# snc98_Display_15x7-Seg_3-digit_LTD040.net
KiCad netlist of a schematic drawn in EAGLE
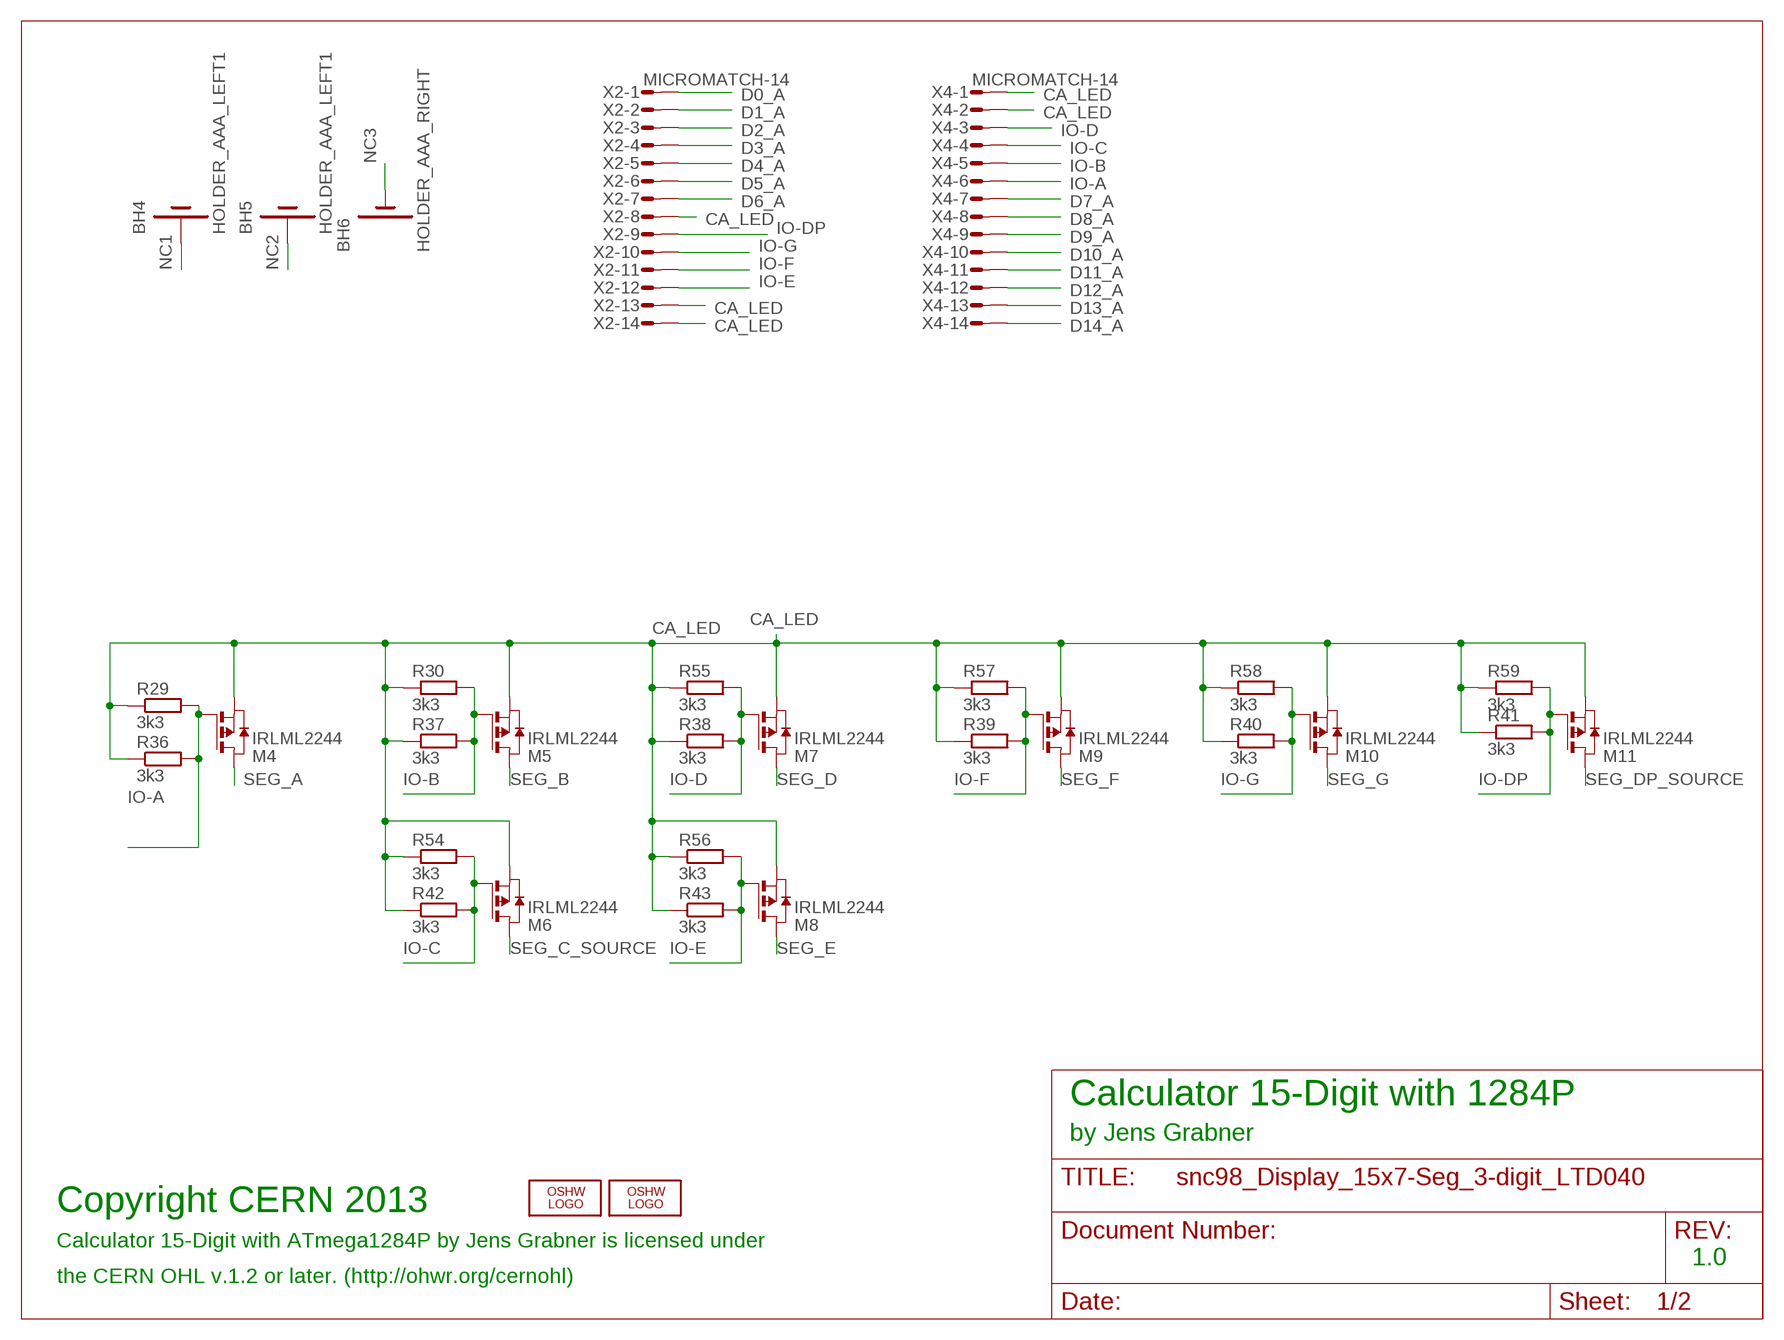
[diagram p0: schematic, sheet 1]
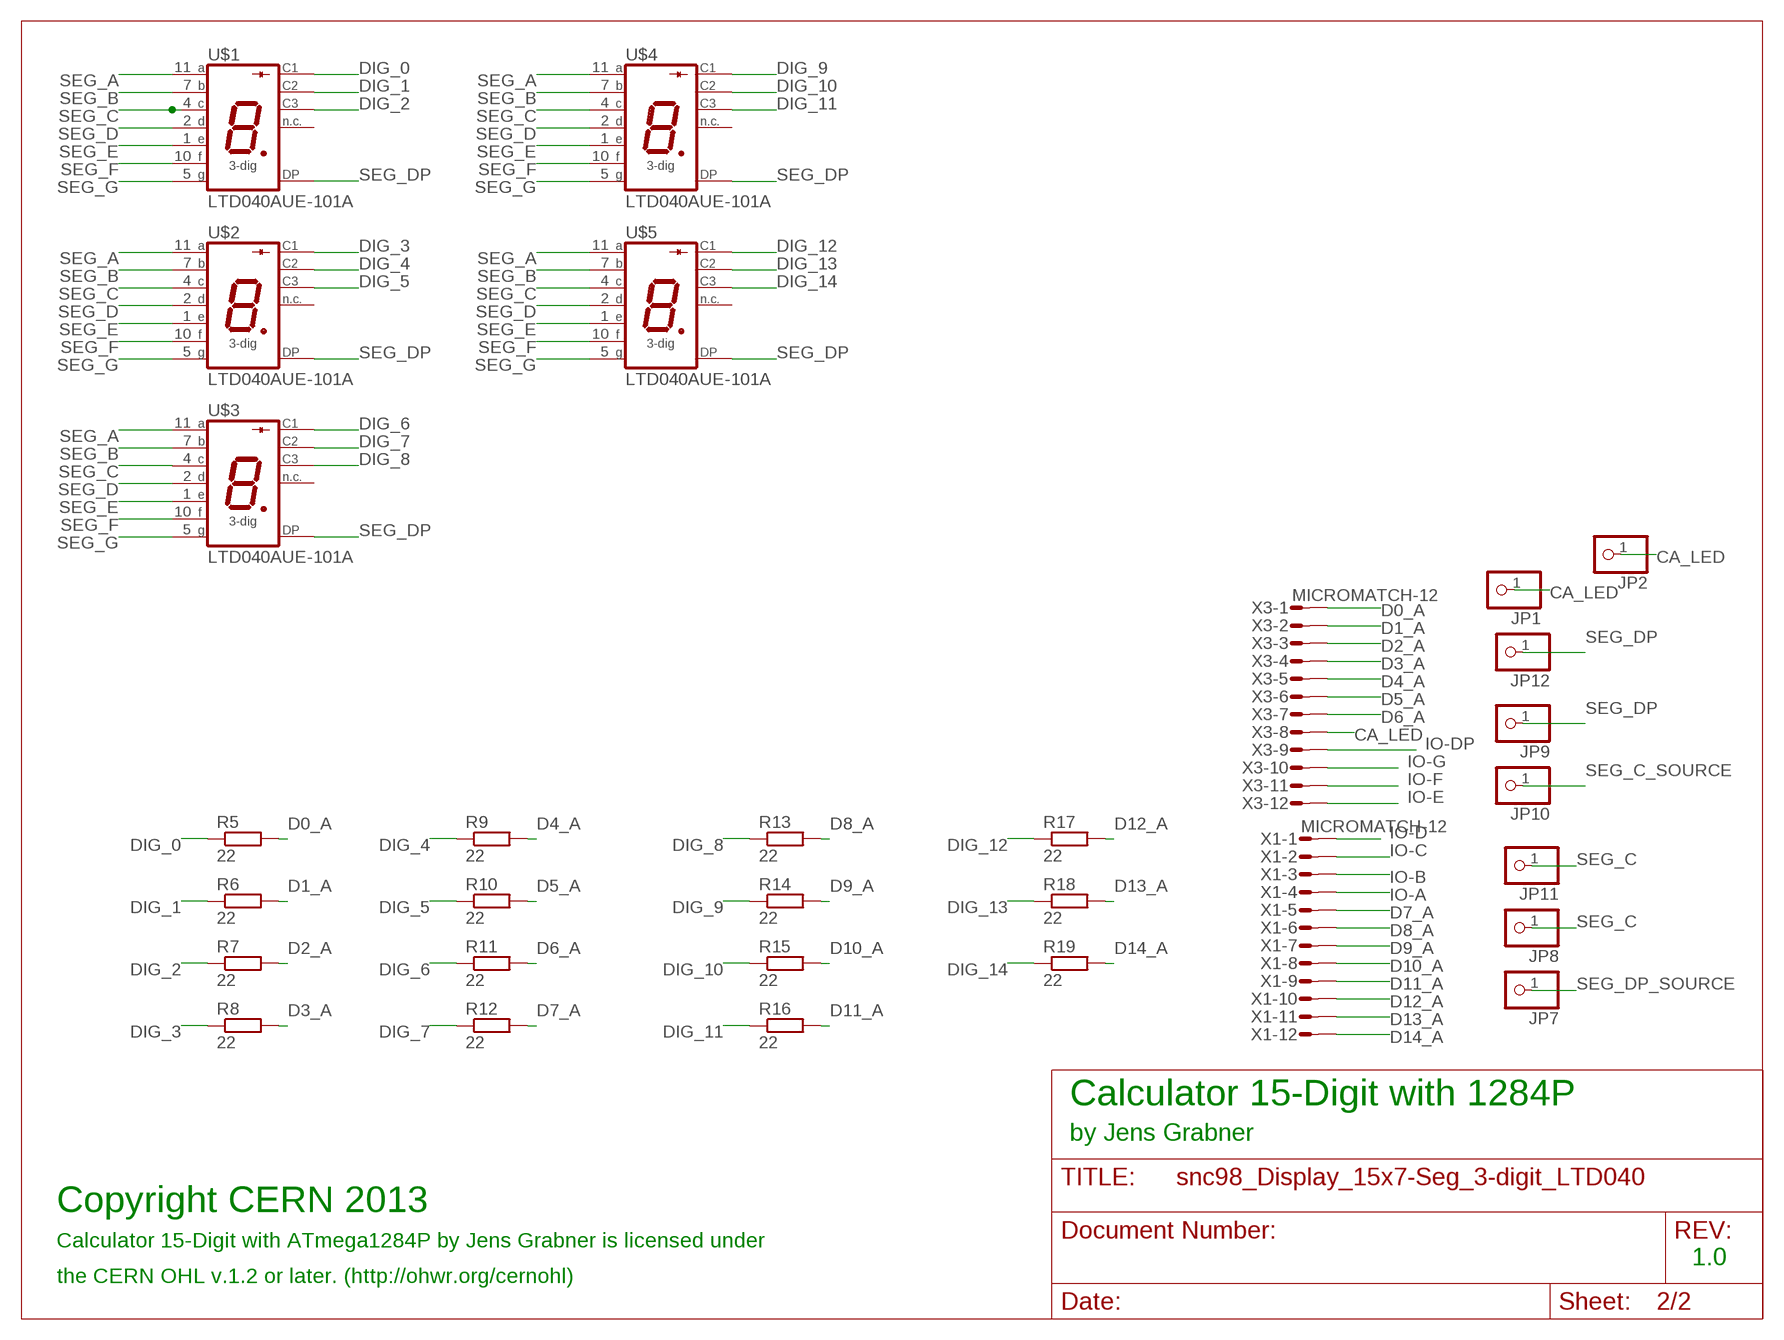
[diagram p1: schematic, sheet 2]

(export (version "E")
  (design (tool "Eeschema 10.0.6"))
  (components
    (comp (ref "JP1")
      (value "PINHD-1X1")
      (footprint "eagle-import:1X01")
      (libsource (lib "eagle-import") (part "PINHD-1X1"))
    )
    (comp (ref "JP2")
      (value "PINHD-1X1")
      (footprint "eagle-import:1X01")
      (libsource (lib "eagle-import") (part "PINHD-1X1"))
    )
    (comp (ref "JP7")
      (value "PINHD-1X1")
      (footprint "eagle-import:1X01")
      (libsource (lib "eagle-import") (part "PINHD-1X1"))
    )
    (comp (ref "JP8")
      (value "PINHD-1X1")
      (footprint "eagle-import:1X01")
      (libsource (lib "eagle-import") (part "PINHD-1X1"))
    )
    (comp (ref "JP9")
      (value "PINHD-1X1")
      (footprint "eagle-import:1X01")
      (libsource (lib "eagle-import") (part "PINHD-1X1"))
    )
    (comp (ref "JP10")
      (value "PINHD-1X1")
      (footprint "eagle-import:1X01")
      (libsource (lib "eagle-import") (part "PINHD-1X1"))
    )
    (comp (ref "JP11")
      (value "PINHD-1X1")
      (footprint "eagle-import:1X01")
      (libsource (lib "eagle-import") (part "PINHD-1X1"))
    )
    (comp (ref "JP12")
      (value "PINHD-1X1")
      (footprint "eagle-import:1X01")
      (libsource (lib "eagle-import") (part "PINHD-1X1"))
    )
    (comp (ref "R5")
      (value "22")
      (footprint "eagle-import:R1210")
      (libsource (lib "eagle-import") (part "R-EU_R1210"))
    )
    (comp (ref "R6")
      (value "22")
      (footprint "eagle-import:R1210")
      (libsource (lib "eagle-import") (part "R-EU_R1210"))
    )
    (comp (ref "R7")
      (value "22")
      (footprint "eagle-import:R1210")
      (libsource (lib "eagle-import") (part "R-EU_R1210"))
    )
    (comp (ref "R8")
      (value "22")
      (footprint "eagle-import:R1210")
      (libsource (lib "eagle-import") (part "R-EU_R1210"))
    )
    (comp (ref "R9")
      (value "22")
      (footprint "eagle-import:R1210")
      (libsource (lib "eagle-import") (part "R-EU_R1210"))
    )
    (comp (ref "R10")
      (value "22")
      (footprint "eagle-import:R1210")
      (libsource (lib "eagle-import") (part "R-EU_R1210"))
    )
    (comp (ref "R11")
      (value "22")
      (footprint "eagle-import:R1210")
      (libsource (lib "eagle-import") (part "R-EU_R1210"))
    )
    (comp (ref "R12")
      (value "22")
      (footprint "eagle-import:R1210")
      (libsource (lib "eagle-import") (part "R-EU_R1210"))
    )
    (comp (ref "R13")
      (value "22")
      (footprint "eagle-import:R1210")
      (libsource (lib "eagle-import") (part "R-EU_R1210"))
    )
    (comp (ref "R14")
      (value "22")
      (footprint "eagle-import:R1210")
      (libsource (lib "eagle-import") (part "R-EU_R1210"))
    )
    (comp (ref "R15")
      (value "22")
      (footprint "eagle-import:R1210")
      (libsource (lib "eagle-import") (part "R-EU_R1210"))
    )
    (comp (ref "R16")
      (value "22")
      (footprint "eagle-import:R1210")
      (libsource (lib "eagle-import") (part "R-EU_R1210"))
    )
    (comp (ref "R17")
      (value "22")
      (footprint "eagle-import:R1210")
      (libsource (lib "eagle-import") (part "R-EU_R1210"))
    )
    (comp (ref "R18")
      (value "22")
      (footprint "eagle-import:R1210")
      (libsource (lib "eagle-import") (part "R-EU_R1210"))
    )
    (comp (ref "R19")
      (value "22")
      (footprint "eagle-import:R1210")
      (libsource (lib "eagle-import") (part "R-EU_R1210"))
    )
    (comp (ref "U$1")
      (value "LTD040AUE-101A")
      (footprint "eagle-import:LTD040AUE-101A")
      (libsource (lib "eagle-import") (part "LTD040AUE-101A"))
    )
    (comp (ref "U$2")
      (value "LTD040AUE-101A")
      (footprint "eagle-import:LTD040AUE-101A")
      (libsource (lib "eagle-import") (part "LTD040AUE-101A"))
    )
    (comp (ref "U$3")
      (value "LTD040AUE-101A")
      (footprint "eagle-import:LTD040AUE-101A")
      (libsource (lib "eagle-import") (part "LTD040AUE-101A"))
    )
    (comp (ref "U$4")
      (value "LTD040AUE-101A")
      (footprint "eagle-import:LTD040AUE-101A")
      (libsource (lib "eagle-import") (part "LTD040AUE-101A"))
    )
    (comp (ref "U$5")
      (value "LTD040AUE-101A")
      (footprint "eagle-import:LTD040AUE-101A")
      (libsource (lib "eagle-import") (part "LTD040AUE-101A"))
    )
    (comp (ref "X1")
      (value "MICROMATCH-12")
      (footprint "eagle-import:MICROMATCH-12")
      (fields (field (name "MF") "FARNELL") (field (name "MPN") "8-215464-2"))
      (libsource (lib "eagle-import") (part "MICROMATCH-12"))
    )
    (comp (ref "X3")
      (value "MICROMATCH-12")
      (footprint "eagle-import:MICROMATCH-12")
      (fields (field (name "MF") "FARNELL") (field (name "MPN") "8-215464-2"))
      (libsource (lib "eagle-import") (part "MICROMATCH-12"))
    )
    (comp (ref "BH4")
      (value "HOLDER_AAA_LEFT1")
      (footprint "eagle-import:BATTERY-AAA-LEFT")
      (libsource (lib "eagle-import") (part "HOLDER_AAA_LEFT1"))
    )
    (comp (ref "BH5")
      (value "HOLDER_AAA_LEFT1")
      (footprint "eagle-import:BATTERY-AAA-LEFT")
      (libsource (lib "eagle-import") (part "HOLDER_AAA_LEFT1"))
    )
    (comp (ref "BH6")
      (value "HOLDER_AAA_RIGHT")
      (footprint "eagle-import:BATTERY-AAA-RIGHT")
      (libsource (lib "eagle-import") (part "HOLDER_AAA_RIGHT"))
    )
    (comp (ref "LOGO1")
      (value "OSHW_LOGO_8MILX0150-NT")
      (footprint "eagle-import:OSHW_8X150_NOTEXT")
      (libsource (lib "eagle-import") (part "OSHW_LOGO_8MILX0150-NT"))
    )
    (comp (ref "LOGO3")
      (value "OSHW_LOGO_6MILX0100-NT")
      (footprint "eagle-import:OSHW_6X100_NOTEXT")
      (libsource (lib "eagle-import") (part "OSHW_LOGO_6MILX0100-NT"))
    )
    (comp (ref "M4")
      (value "IRLML2244")
      (footprint "eagle-import:SOT-23")
      (libsource (lib "eagle-import") (part "IRLML6402"))
    )
    (comp (ref "M5")
      (value "IRLML2244")
      (footprint "eagle-import:SOT-23")
      (libsource (lib "eagle-import") (part "IRLML6402"))
    )
    (comp (ref "M6")
      (value "IRLML2244")
      (footprint "eagle-import:SOT-23")
      (libsource (lib "eagle-import") (part "IRLML6402"))
    )
    (comp (ref "M7")
      (value "IRLML2244")
      (footprint "eagle-import:SOT-23")
      (libsource (lib "eagle-import") (part "IRLML6402"))
    )
    (comp (ref "M8")
      (value "IRLML2244")
      (footprint "eagle-import:SOT-23")
      (libsource (lib "eagle-import") (part "IRLML6402"))
    )
    (comp (ref "M9")
      (value "IRLML2244")
      (footprint "eagle-import:SOT-23")
      (libsource (lib "eagle-import") (part "IRLML6402"))
    )
    (comp (ref "M10")
      (value "IRLML2244")
      (footprint "eagle-import:SOT-23")
      (libsource (lib "eagle-import") (part "IRLML6402"))
    )
    (comp (ref "M11")
      (value "IRLML2244")
      (footprint "eagle-import:SOT-23")
      (libsource (lib "eagle-import") (part "IRLML6402"))
    )
    (comp (ref "R29")
      (value "3k3")
      (footprint "eagle-import:0204_5")
      (libsource (lib "eagle-import") (part "R-EU_0204/5"))
    )
    (comp (ref "R30")
      (value "3k3")
      (footprint "eagle-import:0204_5")
      (libsource (lib "eagle-import") (part "R-EU_0204/5"))
    )
    (comp (ref "R36")
      (value "3k3")
      (footprint "eagle-import:R1206")
      (libsource (lib "eagle-import") (part "R-EU_R1206"))
    )
    (comp (ref "R37")
      (value "3k3")
      (footprint "eagle-import:R1206")
      (libsource (lib "eagle-import") (part "R-EU_R1206"))
    )
    (comp (ref "R38")
      (value "3k3")
      (footprint "eagle-import:R1206")
      (libsource (lib "eagle-import") (part "R-EU_R1206"))
    )
    (comp (ref "R39")
      (value "3k3")
      (footprint "eagle-import:R1206")
      (libsource (lib "eagle-import") (part "R-EU_R1206"))
    )
    (comp (ref "R40")
      (value "3k3")
      (footprint "eagle-import:R1206")
      (libsource (lib "eagle-import") (part "R-EU_R1206"))
    )
    (comp (ref "R41")
      (value "3k3")
      (footprint "eagle-import:R1206")
      (libsource (lib "eagle-import") (part "R-EU_R1206"))
    )
    (comp (ref "R42")
      (value "3k3")
      (footprint "eagle-import:R1206")
      (libsource (lib "eagle-import") (part "R-EU_R1206"))
    )
    (comp (ref "R43")
      (value "3k3")
      (footprint "eagle-import:R1206")
      (libsource (lib "eagle-import") (part "R-EU_R1206"))
    )
    (comp (ref "R54")
      (value "3k3")
      (footprint "eagle-import:0204_5")
      (libsource (lib "eagle-import") (part "R-EU_0204/5"))
    )
    (comp (ref "R55")
      (value "3k3")
      (footprint "eagle-import:0204_5")
      (libsource (lib "eagle-import") (part "R-EU_0204/5"))
    )
    (comp (ref "R56")
      (value "3k3")
      (footprint "eagle-import:0204_5")
      (libsource (lib "eagle-import") (part "R-EU_0204/5"))
    )
    (comp (ref "R57")
      (value "3k3")
      (footprint "eagle-import:0204_5")
      (libsource (lib "eagle-import") (part "R-EU_0204/5"))
    )
    (comp (ref "R58")
      (value "3k3")
      (footprint "eagle-import:0204_5")
      (libsource (lib "eagle-import") (part "R-EU_0204/5"))
    )
    (comp (ref "R59")
      (value "3k3")
      (footprint "eagle-import:0204_5")
      (libsource (lib "eagle-import") (part "R-EU_0204/5"))
    )
    (comp (ref "X2")
      (value "MICROMATCH-14")
      (footprint "eagle-import:MICROMATCH-14")
      (fields (field (name "MF") "FARNELL") (field (name "MPN") "8-215464-4"))
      (libsource (lib "eagle-import") (part "MICROMATCH-14"))
    )
    (comp (ref "X4")
      (value "MICROMATCH-14")
      (footprint "eagle-import:MICROMATCH-14")
      (fields (field (name "MF") "FARNELL") (field (name "MPN") "8-215464-4"))
      (libsource (lib "eagle-import") (part "MICROMATCH-14"))
    )
  )
  (nets
    (net (code "1") (name "CA_LED") (class "Default")
      (node (ref "JP1") (pin "1") (pinfunction "1_1") (pintype "passive"))
      (node (ref "JP2") (pin "1") (pinfunction "1_1") (pintype "passive"))
      (node (ref "M10") (pin "2") (pinfunction "S_2") (pintype "passive"))
      (node (ref "M11") (pin "2") (pinfunction "S_2") (pintype "passive"))
      (node (ref "M4") (pin "2") (pinfunction "S_2") (pintype "passive"))
      (node (ref "M5") (pin "2") (pinfunction "S_2") (pintype "passive"))
      (node (ref "M6") (pin "2") (pinfunction "S_2") (pintype "passive"))
      (node (ref "M7") (pin "2") (pinfunction "S_2") (pintype "passive"))
      (node (ref "M8") (pin "2") (pinfunction "S_2") (pintype "passive"))
      (node (ref "M9") (pin "2") (pinfunction "S_2") (pintype "passive"))
      (node (ref "R29") (pin "1") (pinfunction "1_1") (pintype "passive"))
      (node (ref "R30") (pin "1") (pinfunction "1_1") (pintype "passive"))
      (node (ref "R36") (pin "1") (pinfunction "1_1") (pintype "passive"))
      (node (ref "R37") (pin "1") (pinfunction "1_1") (pintype "passive"))
      (node (ref "R38") (pin "1") (pinfunction "1_1") (pintype "passive"))
      (node (ref "R39") (pin "1") (pinfunction "1_1") (pintype "passive"))
      (node (ref "R40") (pin "1") (pinfunction "1_1") (pintype "passive"))
      (node (ref "R41") (pin "1") (pinfunction "1_1") (pintype "passive"))
      (node (ref "R42") (pin "1") (pinfunction "1_1") (pintype "passive"))
      (node (ref "R43") (pin "1") (pinfunction "1_1") (pintype "passive"))
      (node (ref "R54") (pin "1") (pinfunction "1_1") (pintype "passive"))
      (node (ref "R55") (pin "1") (pinfunction "1_1") (pintype "passive"))
      (node (ref "R56") (pin "1") (pinfunction "1_1") (pintype "passive"))
      (node (ref "R57") (pin "1") (pinfunction "1_1") (pintype "passive"))
      (node (ref "R58") (pin "1") (pinfunction "1_1") (pintype "passive"))
      (node (ref "R59") (pin "1") (pinfunction "1_1") (pintype "passive"))
      (node (ref "X2") (pin "13") (pinfunction "S_13") (pintype "passive"))
      (node (ref "X2") (pin "14") (pinfunction "S_14") (pintype "passive"))
      (node (ref "X2") (pin "8") (pinfunction "S_8") (pintype "passive"))
      (node (ref "X3") (pin "8") (pinfunction "S_8") (pintype "passive"))
      (node (ref "X4") (pin "1") (pinfunction "S_1") (pintype "passive"))
      (node (ref "X4") (pin "2") (pinfunction "S_2") (pintype "passive"))
    )
    (net (code "2") (name "D0_A") (class "Default")
      (node (ref "R5") (pin "2") (pinfunction "2_2") (pintype "passive"))
      (node (ref "X2") (pin "1") (pinfunction "S_1") (pintype "passive"))
      (node (ref "X3") (pin "1") (pinfunction "S_1") (pintype "passive"))
    )
    (net (code "3") (name "D1_A") (class "Default")
      (node (ref "R6") (pin "2") (pinfunction "2_2") (pintype "passive"))
      (node (ref "X2") (pin "2") (pinfunction "S_2") (pintype "passive"))
      (node (ref "X3") (pin "2") (pinfunction "S_2") (pintype "passive"))
    )
    (net (code "4") (name "D2_A") (class "Default")
      (node (ref "R7") (pin "2") (pinfunction "2_2") (pintype "passive"))
      (node (ref "X2") (pin "3") (pinfunction "S_3") (pintype "passive"))
      (node (ref "X3") (pin "3") (pinfunction "S_3") (pintype "passive"))
    )
    (net (code "5") (name "D3_A") (class "Default")
      (node (ref "R8") (pin "2") (pinfunction "2_2") (pintype "passive"))
      (node (ref "X2") (pin "4") (pinfunction "S_4") (pintype "passive"))
      (node (ref "X3") (pin "4") (pinfunction "S_4") (pintype "passive"))
    )
    (net (code "6") (name "D4_A") (class "Default")
      (node (ref "R9") (pin "2") (pinfunction "2_2") (pintype "passive"))
      (node (ref "X2") (pin "5") (pinfunction "S_5") (pintype "passive"))
      (node (ref "X3") (pin "5") (pinfunction "S_5") (pintype "passive"))
    )
    (net (code "7") (name "D5_A") (class "Default")
      (node (ref "R10") (pin "2") (pinfunction "2_2") (pintype "passive"))
      (node (ref "X2") (pin "6") (pinfunction "S_6") (pintype "passive"))
      (node (ref "X3") (pin "6") (pinfunction "S_6") (pintype "passive"))
    )
    (net (code "8") (name "D6_A") (class "Default")
      (node (ref "R11") (pin "2") (pinfunction "2_2") (pintype "passive"))
      (node (ref "X2") (pin "7") (pinfunction "S_7") (pintype "passive"))
      (node (ref "X3") (pin "7") (pinfunction "S_7") (pintype "passive"))
    )
    (net (code "9") (name "D7_A") (class "Default")
      (node (ref "R12") (pin "2") (pinfunction "2_2") (pintype "passive"))
      (node (ref "X1") (pin "5") (pinfunction "S_5") (pintype "passive"))
      (node (ref "X4") (pin "7") (pinfunction "S_7") (pintype "passive"))
    )
    (net (code "10") (name "D8_A") (class "Default")
      (node (ref "R13") (pin "2") (pinfunction "2_2") (pintype "passive"))
      (node (ref "X1") (pin "6") (pinfunction "S_6") (pintype "passive"))
      (node (ref "X4") (pin "8") (pinfunction "S_8") (pintype "passive"))
    )
    (net (code "11") (name "D9_A") (class "Default")
      (node (ref "R14") (pin "2") (pinfunction "2_2") (pintype "passive"))
      (node (ref "X1") (pin "7") (pinfunction "S_7") (pintype "passive"))
      (node (ref "X4") (pin "9") (pinfunction "S_9") (pintype "passive"))
    )
    (net (code "12") (name "D10_A") (class "Default")
      (node (ref "R15") (pin "2") (pinfunction "2_2") (pintype "passive"))
      (node (ref "X1") (pin "8") (pinfunction "S_8") (pintype "passive"))
      (node (ref "X4") (pin "10") (pinfunction "S_10") (pintype "passive"))
    )
    (net (code "13") (name "D11_A") (class "Default")
      (node (ref "R16") (pin "2") (pinfunction "2_2") (pintype "passive"))
      (node (ref "X1") (pin "9") (pinfunction "S_9") (pintype "passive"))
      (node (ref "X4") (pin "11") (pinfunction "S_11") (pintype "passive"))
    )
    (net (code "14") (name "D12_A") (class "Default")
      (node (ref "R17") (pin "2") (pinfunction "2_2") (pintype "passive"))
      (node (ref "X1") (pin "10") (pinfunction "S_10") (pintype "passive"))
      (node (ref "X4") (pin "12") (pinfunction "S_12") (pintype "passive"))
    )
    (net (code "15") (name "D13_A") (class "Default")
      (node (ref "R18") (pin "2") (pinfunction "2_2") (pintype "passive"))
      (node (ref "X1") (pin "11") (pinfunction "S_11") (pintype "passive"))
      (node (ref "X4") (pin "13") (pinfunction "S_13") (pintype "passive"))
    )
    (net (code "16") (name "D14_A") (class "Default")
      (node (ref "R19") (pin "2") (pinfunction "2_2") (pintype "passive"))
      (node (ref "X1") (pin "12") (pinfunction "S_12") (pintype "passive"))
      (node (ref "X4") (pin "14") (pinfunction "S_14") (pintype "passive"))
    )
    (net (code "17") (name "DIG_0") (class "Default")
      (node (ref "R5") (pin "1") (pinfunction "1_1") (pintype "passive"))
      (node (ref "U$1") (pin "12") (pinfunction "C1_12") (pintype "passive"))
    )
    (net (code "18") (name "DIG_1") (class "Default")
      (node (ref "R6") (pin "1") (pinfunction "1_1") (pintype "passive"))
      (node (ref "U$1") (pin "9") (pinfunction "C2_9") (pintype "passive"))
    )
    (net (code "19") (name "DIG_2") (class "Default")
      (node (ref "R7") (pin "1") (pinfunction "1_1") (pintype "passive"))
      (node (ref "U$1") (pin "8") (pinfunction "C3_8") (pintype "passive"))
    )
    (net (code "20") (name "DIG_3") (class "Default")
      (node (ref "R8") (pin "1") (pinfunction "1_1") (pintype "passive"))
      (node (ref "U$2") (pin "12") (pinfunction "C1_12") (pintype "passive"))
    )
    (net (code "21") (name "DIG_4") (class "Default")
      (node (ref "R9") (pin "1") (pinfunction "1_1") (pintype "passive"))
      (node (ref "U$2") (pin "9") (pinfunction "C2_9") (pintype "passive"))
    )
    (net (code "22") (name "DIG_5") (class "Default")
      (node (ref "R10") (pin "1") (pinfunction "1_1") (pintype "passive"))
      (node (ref "U$2") (pin "8") (pinfunction "C3_8") (pintype "passive"))
    )
    (net (code "23") (name "DIG_6") (class "Default")
      (node (ref "R11") (pin "1") (pinfunction "1_1") (pintype "passive"))
      (node (ref "U$3") (pin "12") (pinfunction "C1_12") (pintype "passive"))
    )
    (net (code "24") (name "DIG_7") (class "Default")
      (node (ref "R12") (pin "1") (pinfunction "1_1") (pintype "passive"))
      (node (ref "U$3") (pin "9") (pinfunction "C2_9") (pintype "passive"))
    )
    (net (code "25") (name "DIG_8") (class "Default")
      (node (ref "R13") (pin "1") (pinfunction "1_1") (pintype "passive"))
      (node (ref "U$3") (pin "8") (pinfunction "C3_8") (pintype "passive"))
    )
    (net (code "26") (name "DIG_9") (class "Default")
      (node (ref "R14") (pin "1") (pinfunction "1_1") (pintype "passive"))
      (node (ref "U$4") (pin "12") (pinfunction "C1_12") (pintype "passive"))
    )
    (net (code "27") (name "DIG_10") (class "Default")
      (node (ref "R15") (pin "1") (pinfunction "1_1") (pintype "passive"))
      (node (ref "U$4") (pin "9") (pinfunction "C2_9") (pintype "passive"))
    )
    (net (code "28") (name "DIG_11") (class "Default")
      (node (ref "R16") (pin "1") (pinfunction "1_1") (pintype "passive"))
      (node (ref "U$4") (pin "8") (pinfunction "C3_8") (pintype "passive"))
    )
    (net (code "29") (name "DIG_12") (class "Default")
      (node (ref "R17") (pin "1") (pinfunction "1_1") (pintype "passive"))
      (node (ref "U$5") (pin "12") (pinfunction "C1_12") (pintype "passive"))
    )
    (net (code "30") (name "DIG_13") (class "Default")
      (node (ref "R18") (pin "1") (pinfunction "1_1") (pintype "passive"))
      (node (ref "U$5") (pin "9") (pinfunction "C2_9") (pintype "passive"))
    )
    (net (code "31") (name "DIG_14") (class "Default")
      (node (ref "R19") (pin "1") (pinfunction "1_1") (pintype "passive"))
      (node (ref "U$5") (pin "8") (pinfunction "C3_8") (pintype "passive"))
    )
    (net (code "32") (name "IO-A") (class "Default")
      (node (ref "M4") (pin "1") (pinfunction "G_1") (pintype "passive"))
      (node (ref "R29") (pin "2") (pinfunction "2_2") (pintype "passive"))
      (node (ref "R36") (pin "2") (pinfunction "2_2") (pintype "passive"))
      (node (ref "X1") (pin "4") (pinfunction "S_4") (pintype "passive"))
      (node (ref "X4") (pin "6") (pinfunction "S_6") (pintype "passive"))
    )
    (net (code "33") (name "IO-B") (class "Default")
      (node (ref "M5") (pin "1") (pinfunction "G_1") (pintype "passive"))
      (node (ref "R30") (pin "2") (pinfunction "2_2") (pintype "passive"))
      (node (ref "R37") (pin "2") (pinfunction "2_2") (pintype "passive"))
      (node (ref "X1") (pin "3") (pinfunction "S_3") (pintype "passive"))
      (node (ref "X4") (pin "5") (pinfunction "S_5") (pintype "passive"))
    )
    (net (code "34") (name "IO-C") (class "Default")
      (node (ref "M6") (pin "1") (pinfunction "G_1") (pintype "passive"))
      (node (ref "R42") (pin "2") (pinfunction "2_2") (pintype "passive"))
      (node (ref "R54") (pin "2") (pinfunction "2_2") (pintype "passive"))
      (node (ref "X1") (pin "2") (pinfunction "S_2") (pintype "passive"))
      (node (ref "X4") (pin "4") (pinfunction "S_4") (pintype "passive"))
    )
    (net (code "35") (name "IO-D") (class "Default")
      (node (ref "M7") (pin "1") (pinfunction "G_1") (pintype "passive"))
      (node (ref "R38") (pin "2") (pinfunction "2_2") (pintype "passive"))
      (node (ref "R55") (pin "2") (pinfunction "2_2") (pintype "passive"))
      (node (ref "X1") (pin "1") (pinfunction "S_1") (pintype "passive"))
      (node (ref "X4") (pin "3") (pinfunction "S_3") (pintype "passive"))
    )
    (net (code "36") (name "IO-DP") (class "Default")
      (node (ref "M11") (pin "1") (pinfunction "G_1") (pintype "passive"))
      (node (ref "R41") (pin "2") (pinfunction "2_2") (pintype "passive"))
      (node (ref "R59") (pin "2") (pinfunction "2_2") (pintype "passive"))
      (node (ref "X2") (pin "9") (pinfunction "S_9") (pintype "passive"))
      (node (ref "X3") (pin "9") (pinfunction "S_9") (pintype "passive"))
    )
    (net (code "37") (name "IO-E") (class "Default")
      (node (ref "M8") (pin "1") (pinfunction "G_1") (pintype "passive"))
      (node (ref "R43") (pin "2") (pinfunction "2_2") (pintype "passive"))
      (node (ref "R56") (pin "2") (pinfunction "2_2") (pintype "passive"))
      (node (ref "X2") (pin "12") (pinfunction "S_12") (pintype "passive"))
      (node (ref "X3") (pin "12") (pinfunction "S_12") (pintype "passive"))
    )
    (net (code "38") (name "IO-F") (class "Default")
      (node (ref "M9") (pin "1") (pinfunction "G_1") (pintype "passive"))
      (node (ref "R39") (pin "2") (pinfunction "2_2") (pintype "passive"))
      (node (ref "R57") (pin "2") (pinfunction "2_2") (pintype "passive"))
      (node (ref "X2") (pin "11") (pinfunction "S_11") (pintype "passive"))
      (node (ref "X3") (pin "11") (pinfunction "S_11") (pintype "passive"))
    )
    (net (code "39") (name "IO-G") (class "Default")
      (node (ref "M10") (pin "1") (pinfunction "G_1") (pintype "passive"))
      (node (ref "R40") (pin "2") (pinfunction "2_2") (pintype "passive"))
      (node (ref "R58") (pin "2") (pinfunction "2_2") (pintype "passive"))
      (node (ref "X2") (pin "10") (pinfunction "S_10") (pintype "passive"))
      (node (ref "X3") (pin "10") (pinfunction "S_10") (pintype "passive"))
    )
    (net (code "40") (name "NC1") (class "Default")
      (node (ref "BH4") (pin "P1") (pinfunction "+_P1") (pintype "power_in"))
      (node (ref "BH4") (pin "P2") (pinfunction "+_P2") (pintype "power_in"))
      (node (ref "BH4") (pin "P3") (pinfunction "+_P3") (pintype "power_in"))
      (node (ref "BH4") (pin "P4") (pinfunction "+_P4") (pintype "power_in"))
    )
    (net (code "41") (name "NC2") (class "Default")
      (node (ref "BH5") (pin "P1") (pinfunction "+_P1") (pintype "power_in"))
      (node (ref "BH5") (pin "P2") (pinfunction "+_P2") (pintype "power_in"))
      (node (ref "BH5") (pin "P3") (pinfunction "+_P3") (pintype "power_in"))
      (node (ref "BH5") (pin "P4") (pinfunction "+_P4") (pintype "power_in"))
    )
    (net (code "42") (name "NC3") (class "Default")
      (node (ref "BH6") (pin "M1") (pinfunction "-_M1") (pintype "power_in"))
      (node (ref "BH6") (pin "M2") (pinfunction "-_M2") (pintype "power_in"))
      (node (ref "BH6") (pin "M3") (pinfunction "-_M3") (pintype "power_in"))
      (node (ref "BH6") (pin "M4") (pinfunction "-_M4") (pintype "power_in"))
    )
    (net (code "43") (name "SEG_A") (class "Default")
      (node (ref "M4") (pin "3") (pinfunction "D_3") (pintype "passive"))
      (node (ref "U$1") (pin "11") (pinfunction "A_11") (pintype "passive"))
      (node (ref "U$2") (pin "11") (pinfunction "A_11") (pintype "passive"))
      (node (ref "U$3") (pin "11") (pinfunction "A_11") (pintype "passive"))
      (node (ref "U$4") (pin "11") (pinfunction "A_11") (pintype "passive"))
      (node (ref "U$5") (pin "11") (pinfunction "A_11") (pintype "passive"))
    )
    (net (code "44") (name "SEG_B") (class "Default")
      (node (ref "M5") (pin "3") (pinfunction "D_3") (pintype "passive"))
      (node (ref "U$1") (pin "7") (pinfunction "B_7") (pintype "passive"))
      (node (ref "U$2") (pin "7") (pinfunction "B_7") (pintype "passive"))
      (node (ref "U$3") (pin "7") (pinfunction "B_7") (pintype "passive"))
      (node (ref "U$4") (pin "7") (pinfunction "B_7") (pintype "passive"))
      (node (ref "U$5") (pin "7") (pinfunction "B_7") (pintype "passive"))
    )
    (net (code "45") (name "SEG_C") (class "Default")
      (node (ref "JP11") (pin "1") (pinfunction "1_1") (pintype "passive"))
      (node (ref "JP8") (pin "1") (pinfunction "1_1") (pintype "passive"))
      (node (ref "U$1") (pin "4") (pinfunction "C_4") (pintype "passive"))
      (node (ref "U$2") (pin "4") (pinfunction "C_4") (pintype "passive"))
      (node (ref "U$3") (pin "4") (pinfunction "C_4") (pintype "passive"))
      (node (ref "U$4") (pin "4") (pinfunction "C_4") (pintype "passive"))
      (node (ref "U$5") (pin "4") (pinfunction "C_4") (pintype "passive"))
    )
    (net (code "46") (name "SEG_C_SOURCE") (class "Default")
      (node (ref "JP10") (pin "1") (pinfunction "1_1") (pintype "passive"))
      (node (ref "M6") (pin "3") (pinfunction "D_3") (pintype "passive"))
    )
    (net (code "47") (name "SEG_D") (class "Default")
      (node (ref "M7") (pin "3") (pinfunction "D_3") (pintype "passive"))
      (node (ref "U$1") (pin "2") (pinfunction "D_2") (pintype "passive"))
      (node (ref "U$2") (pin "2") (pinfunction "D_2") (pintype "passive"))
      (node (ref "U$3") (pin "2") (pinfunction "D_2") (pintype "passive"))
      (node (ref "U$4") (pin "2") (pinfunction "D_2") (pintype "passive"))
      (node (ref "U$5") (pin "2") (pinfunction "D_2") (pintype "passive"))
    )
    (net (code "48") (name "SEG_DP") (class "Default")
      (node (ref "JP12") (pin "1") (pinfunction "1_1") (pintype "passive"))
      (node (ref "JP9") (pin "1") (pinfunction "1_1") (pintype "passive"))
      (node (ref "U$1") (pin "3") (pinfunction "DP_3") (pintype "passive"))
      (node (ref "U$2") (pin "3") (pinfunction "DP_3") (pintype "passive"))
      (node (ref "U$3") (pin "3") (pinfunction "DP_3") (pintype "passive"))
      (node (ref "U$4") (pin "3") (pinfunction "DP_3") (pintype "passive"))
      (node (ref "U$5") (pin "3") (pinfunction "DP_3") (pintype "passive"))
    )
    (net (code "49") (name "SEG_DP_SOURCE") (class "Default")
      (node (ref "JP7") (pin "1") (pinfunction "1_1") (pintype "passive"))
      (node (ref "M11") (pin "3") (pinfunction "D_3") (pintype "passive"))
    )
    (net (code "50") (name "SEG_E") (class "Default")
      (node (ref "M8") (pin "3") (pinfunction "D_3") (pintype "passive"))
      (node (ref "U$1") (pin "1") (pinfunction "E_1") (pintype "passive"))
      (node (ref "U$2") (pin "1") (pinfunction "E_1") (pintype "passive"))
      (node (ref "U$3") (pin "1") (pinfunction "E_1") (pintype "passive"))
      (node (ref "U$4") (pin "1") (pinfunction "E_1") (pintype "passive"))
      (node (ref "U$5") (pin "1") (pinfunction "E_1") (pintype "passive"))
    )
    (net (code "51") (name "SEG_F") (class "Default")
      (node (ref "M9") (pin "3") (pinfunction "D_3") (pintype "passive"))
      (node (ref "U$1") (pin "10") (pinfunction "F_10") (pintype "passive"))
      (node (ref "U$2") (pin "10") (pinfunction "F_10") (pintype "passive"))
      (node (ref "U$3") (pin "10") (pinfunction "F_10") (pintype "passive"))
      (node (ref "U$4") (pin "10") (pinfunction "F_10") (pintype "passive"))
      (node (ref "U$5") (pin "10") (pinfunction "F_10") (pintype "passive"))
    )
    (net (code "52") (name "SEG_G") (class "Default")
      (node (ref "M10") (pin "3") (pinfunction "D_3") (pintype "passive"))
      (node (ref "U$1") (pin "5") (pinfunction "G_5") (pintype "passive"))
      (node (ref "U$2") (pin "5") (pinfunction "G_5") (pintype "passive"))
      (node (ref "U$3") (pin "5") (pinfunction "G_5") (pintype "passive"))
      (node (ref "U$4") (pin "5") (pinfunction "G_5") (pintype "passive"))
      (node (ref "U$5") (pin "5") (pinfunction "G_5") (pintype "passive"))
    )
    (net (code "53") (name "unconnected-(U$1-P$1-Pad6)") (class "Default")
      (node (ref "U$1") (pin "6") (pinfunction "P$1_6") (pintype "passive"))
    )
    (net (code "54") (name "unconnected-(U$2-P$1-Pad6)") (class "Default")
      (node (ref "U$2") (pin "6") (pinfunction "P$1_6") (pintype "passive"))
    )
    (net (code "55") (name "unconnected-(U$3-P$1-Pad6)") (class "Default")
      (node (ref "U$3") (pin "6") (pinfunction "P$1_6") (pintype "passive"))
    )
    (net (code "56") (name "unconnected-(U$4-P$1-Pad6)") (class "Default")
      (node (ref "U$4") (pin "6") (pinfunction "P$1_6") (pintype "passive"))
    )
    (net (code "57") (name "unconnected-(U$5-P$1-Pad6)") (class "Default")
      (node (ref "U$5") (pin "6") (pinfunction "P$1_6") (pintype "passive"))
    )
  )
)
